# MCU.net
KiCad netlist of a schematic drawn in Altium Designer
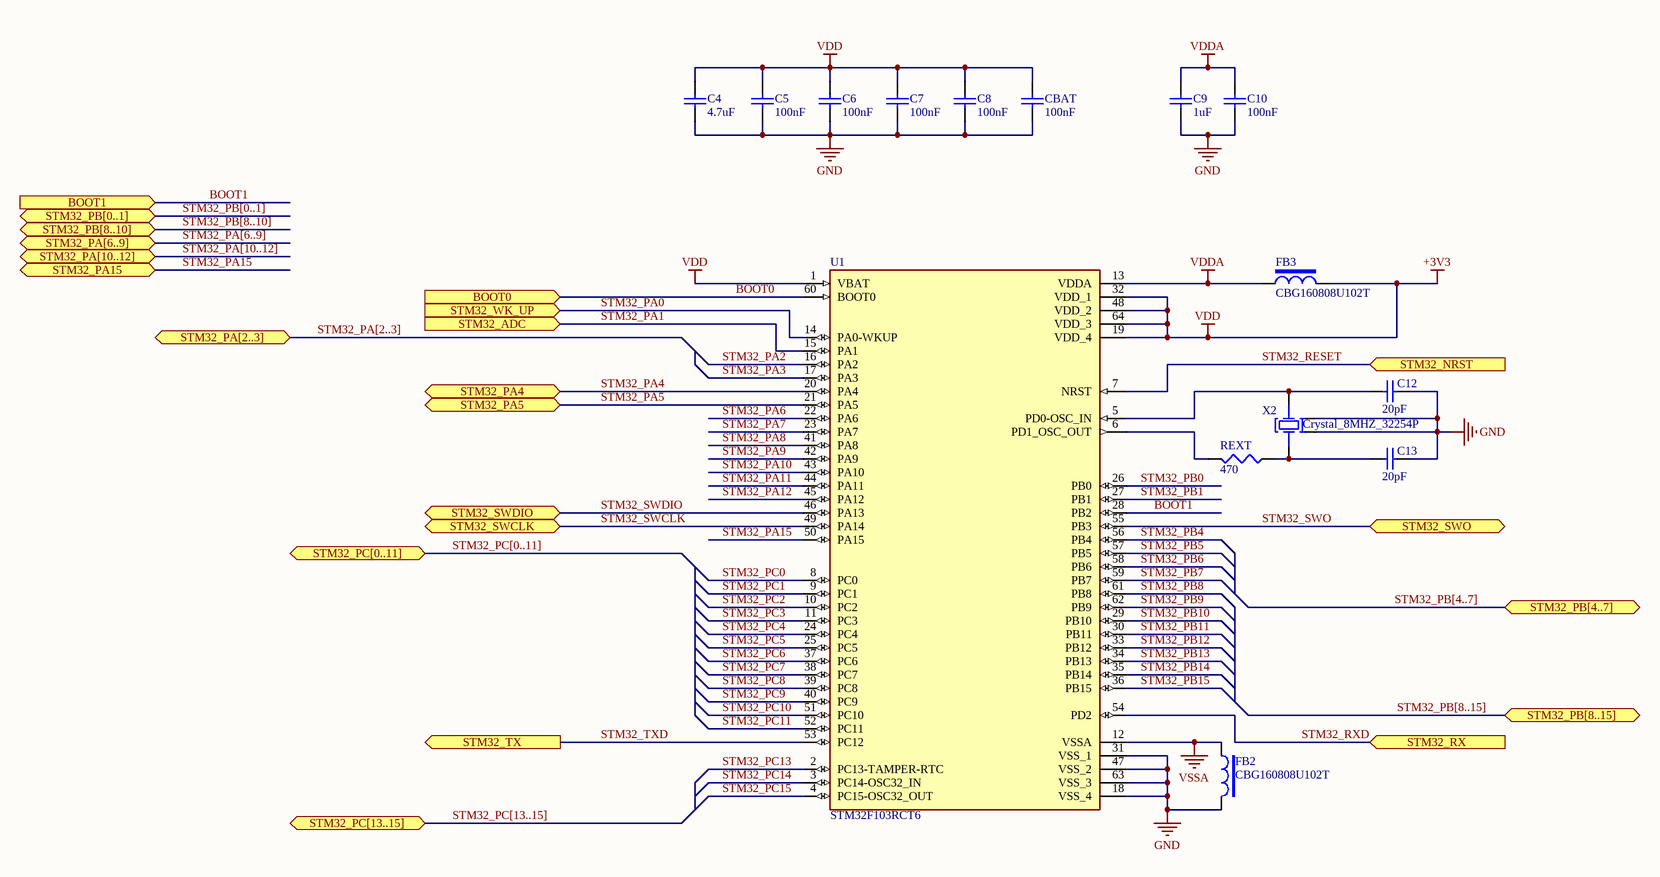
[diagram p0: MCU.SchDoc]

(export (version "E")
  (design (tool "Eeschema 10.0.6"))
  (components
    (comp (ref "C4")
      (value "4.7uF")
      (footprint "CAPC0805(2012)145_L")
      (description "Chip Capacitor, 100nF +/-40%, 16V, 0805, Thickness 1.45 mm")
      (fields (field (name "TOLERANCE") "5%") (field (name "Comment") "100nF"))
      (libsource (lib "Ho Chi Minh City University of Technology") (part "CAP-NP-2"))
    )
    (comp (ref "C5")
      (value "100nF")
      (footprint "CAPC0805(2012)145_L")
      (description "Chip Capacitor, 100nF +/-40%, 16V, 0805, Thickness 1.45 mm")
      (fields (field (name "TOLERANCE") "5%"))
      (libsource (lib "Ho Chi Minh City University of Technology") (part "CAP-NP-2"))
    )
    (comp (ref "C6")
      (value "100nF")
      (footprint "CAPC0805(2012)145_L")
      (description "Chip Capacitor, 100nF +/-40%, 16V, 0805, Thickness 1.45 mm")
      (fields (field (name "TOLERANCE") "5%"))
      (libsource (lib "Ho Chi Minh City University of Technology") (part "CAP-NP-2"))
    )
    (comp (ref "C7")
      (value "100nF")
      (footprint "CAPC0805(2012)145_L")
      (description "Chip Capacitor, 100nF +/-40%, 16V, 0805, Thickness 1.45 mm")
      (fields (field (name "TOLERANCE") "5%"))
      (libsource (lib "Ho Chi Minh City University of Technology") (part "CAP-NP-2"))
    )
    (comp (ref "C8")
      (value "100nF")
      (footprint "CAPC0805(2012)145_L")
      (description "Chip Capacitor, 100nF +/-40%, 16V, 0805, Thickness 1.45 mm")
      (fields (field (name "TOLERANCE") "5%"))
      (libsource (lib "Ho Chi Minh City University of Technology") (part "CAP-NP-2"))
    )
    (comp (ref "C9")
      (value "1uF")
      (footprint "CAPC0805(2012)145_L")
      (description "Chip Capacitor, 100nF +/-40%, 16V, 0805, Thickness 1.45 mm")
      (fields (field (name "TOLERANCE") "5%") (field (name "Comment") "100nF"))
      (libsource (lib "Ho Chi Minh City University of Technology") (part "CAP-NP-2"))
    )
    (comp (ref "C10")
      (value "100nF")
      (footprint "CAPC0805(2012)145_L")
      (description "Chip Capacitor, 100nF +/-40%, 16V, 0805, Thickness 1.45 mm")
      (fields (field (name "TOLERANCE") "5%"))
      (libsource (lib "Ho Chi Minh City University of Technology") (part "CAP-NP-2"))
    )
    (comp (ref "C12")
      (value "20pF")
      (footprint "CAPC0805(2012)145_L")
      (description "Chip Capacitor, 22µF +/-40%, 16V, 0805, Thickness 1.45 mm")
      (fields (field (name "TOLERANCE") "5%") (field (name "Comment") "22uF"))
      (libsource (lib "Ho Chi Minh City University of Technology") (part "CAP-NP-2"))
    )
    (comp (ref "C13")
      (value "20pF")
      (footprint "CAPC0805(2012)145_L")
      (description "Chip Capacitor, 22µF +/-40%, 16V, 0805, Thickness 1.45 mm")
      (fields (field (name "TOLERANCE") "5%") (field (name "Comment") "22uF"))
      (libsource (lib "Ho Chi Minh City University of Technology") (part "CAP-NP-2"))
    )
    (comp (ref "CBAT")
      (value "100nF")
      (footprint "CAPC0805(2012)145_L")
      (description "Chip Capacitor, 100nF +/-40%, 16V, 0805, Thickness 1.45 mm")
      (fields (field (name "TOLERANCE") "5%"))
      (libsource (lib "Ho Chi Minh City University of Technology") (part "CAP-NP-2"))
    )
    (comp (ref "FB2")
      (value "CBG160808U102T")
      (footprint "0603")
      (description "Oreki")
      (fields (field (name "JLCPCB PART #") "C98501"))
      (libsource (lib "Ho Chi Minh City University of Technology") (part "Ferrite Bead"))
    )
    (comp (ref "FB3")
      (value "CBG160808U102T")
      (footprint "0603")
      (description "Oreki")
      (fields (field (name "JLCPCB PART #") "C98501"))
      (libsource (lib "") (part "Ferrite Bead_1"))
    )
    (comp (ref "REXT")
      (value "470")
      (footprint "0805 (2012 Metric)")
      (description "Oreki")
      (fields (field (name "Comment") "220"))
      (libsource (lib "Ho Chi Minh City University of Technology") (part "RES-2"))
    )
    (comp (ref "U1")
      (value "STM32F103RCT6")
      (footprint "QFP50P1200X1200X160-64N")
      (description "ARMÂ® CortexÂ®-M3 STM32F1 Microcontroller IC 32-Bit 72MHz 256KB (256K x 8) FLASH 64-LQFP (10x10)")
      (fields (field (name "MF") "STMicroelectronics") (field (name "JLCPCB PART #") "C8323"))
      (libsource (lib "Ho Chi Minh City University of Technology") (part "STM32F103RCT6"))
    )
    (comp (ref "X2")
      (value "Crystal_8MHZ_32254P")
      (footprint "4-SMD, No Lead (3.2mm x 2.5mm)")
      (description "SMD3225-4P")
      (fields (field (name "JLCPCB PART #") "C2682774"))
      (libsource (lib "Ho Chi Minh City University of Technology") (part "Crystal"))
    )
  )
  (nets
    (net (code "1") (name "+3V3") (class "Default")
      (node (ref "C4") (pin "2") (pinfunction "2_2") (pintype "passive"))
      (node (ref "C5") (pin "2") (pinfunction "2_2") (pintype "passive"))
      (node (ref "C6") (pin "2") (pinfunction "2_2") (pintype "passive"))
      (node (ref "C7") (pin "2") (pinfunction "2_2") (pintype "passive"))
      (node (ref "C8") (pin "2") (pinfunction "2_2") (pintype "passive"))
      (node (ref "CBAT") (pin "2") (pinfunction "2_2") (pintype "passive"))
      (node (ref "FB3") (pin "2") (pinfunction "2_2") (pintype "passive"))
      (node (ref "U1") (pin "1") (pinfunction "VBAT_1") (pintype "input"))
      (node (ref "U1") (pin "19") (pinfunction "VDD_4_19") (pintype "power_in"))
      (node (ref "U1") (pin "32") (pinfunction "VDD_1_32") (pintype "power_in"))
      (node (ref "U1") (pin "48") (pinfunction "VDD_2_48") (pintype "power_in"))
      (node (ref "U1") (pin "64") (pinfunction "VDD_3_64") (pintype "power_in"))
    )
    (net (code "2") (name "/BOOT0") (class "Default")
      (node (ref "U1") (pin "60") (pinfunction "BOOT0_60") (pintype "input"))
    )
    (net (code "3") (name "/BOOT1") (class "Default")
      (node (ref "U1") (pin "28") (pinfunction "PB2_28") (pintype "bidirectional"))
    )
    (net (code "4") (name "/STM32_PA0") (class "Default")
      (node (ref "U1") (pin "14") (pinfunction "PA0-WKUP_14") (pintype "bidirectional"))
    )
    (net (code "5") (name "/STM32_PA1") (class "Default")
      (node (ref "U1") (pin "15") (pinfunction "PA1_15") (pintype "bidirectional"))
    )
    (net (code "6") (name "/STM32_PA2") (class "Default")
      (node (ref "U1") (pin "16") (pinfunction "PA2_16") (pintype "bidirectional"))
    )
    (net (code "7") (name "/STM32_PA3") (class "Default")
      (node (ref "U1") (pin "17") (pinfunction "PA3_17") (pintype "bidirectional"))
    )
    (net (code "8") (name "/STM32_PA4") (class "Default")
      (node (ref "U1") (pin "20") (pinfunction "PA4_20") (pintype "bidirectional"))
    )
    (net (code "9") (name "/STM32_PA5") (class "Default")
      (node (ref "U1") (pin "21") (pinfunction "PA5_21") (pintype "bidirectional"))
    )
    (net (code "10") (name "/STM32_PA6") (class "Default")
      (node (ref "U1") (pin "22") (pinfunction "PA6_22") (pintype "bidirectional"))
    )
    (net (code "11") (name "/STM32_PA7") (class "Default")
      (node (ref "U1") (pin "23") (pinfunction "PA7_23") (pintype "bidirectional"))
    )
    (net (code "12") (name "/STM32_PA8") (class "Default")
      (node (ref "U1") (pin "41") (pinfunction "PA8_41") (pintype "bidirectional"))
    )
    (net (code "13") (name "/STM32_PA9") (class "Default")
      (node (ref "U1") (pin "42") (pinfunction "PA9_42") (pintype "bidirectional"))
    )
    (net (code "14") (name "/STM32_PA10") (class "Default")
      (node (ref "U1") (pin "43") (pinfunction "PA10_43") (pintype "bidirectional"))
    )
    (net (code "15") (name "/STM32_PA11") (class "Default")
      (node (ref "U1") (pin "44") (pinfunction "PA11_44") (pintype "bidirectional"))
    )
    (net (code "16") (name "/STM32_PA12") (class "Default")
      (node (ref "U1") (pin "45") (pinfunction "PA12_45") (pintype "bidirectional"))
    )
    (net (code "17") (name "/STM32_PA15") (class "Default")
      (node (ref "U1") (pin "50") (pinfunction "PA15_50") (pintype "bidirectional"))
    )
    (net (code "21") (name "/STM32_PB0") (class "Default")
      (node (ref "U1") (pin "26") (pinfunction "PB0_26") (pintype "bidirectional"))
    )
    (net (code "22") (name "/STM32_PB1") (class "Default")
      (node (ref "U1") (pin "27") (pinfunction "PB1_27") (pintype "bidirectional"))
    )
    (net (code "23") (name "/STM32_PB4") (class "Default")
      (node (ref "U1") (pin "56") (pinfunction "PB4_56") (pintype "bidirectional"))
    )
    (net (code "24") (name "/STM32_PB5") (class "Default")
      (node (ref "U1") (pin "57") (pinfunction "PB5_57") (pintype "bidirectional"))
    )
    (net (code "25") (name "/STM32_PB6") (class "Default")
      (node (ref "U1") (pin "58") (pinfunction "PB6_58") (pintype "bidirectional"))
    )
    (net (code "26") (name "/STM32_PB7") (class "Default")
      (node (ref "U1") (pin "59") (pinfunction "PB7_59") (pintype "bidirectional"))
    )
    (net (code "27") (name "/STM32_PB8") (class "Default")
      (node (ref "U1") (pin "61") (pinfunction "PB8_61") (pintype "bidirectional"))
    )
    (net (code "28") (name "/STM32_PB9") (class "Default")
      (node (ref "U1") (pin "62") (pinfunction "PB9_62") (pintype "bidirectional"))
    )
    (net (code "29") (name "/STM32_PB10") (class "Default")
      (node (ref "U1") (pin "29") (pinfunction "PB10_29") (pintype "bidirectional"))
    )
    (net (code "30") (name "/STM32_PB11") (class "Default")
      (node (ref "U1") (pin "30") (pinfunction "PB11_30") (pintype "bidirectional"))
    )
    (net (code "31") (name "/STM32_PB12") (class "Default")
      (node (ref "U1") (pin "33") (pinfunction "PB12_33") (pintype "bidirectional"))
    )
    (net (code "32") (name "/STM32_PB13") (class "Default")
      (node (ref "U1") (pin "34") (pinfunction "PB13_34") (pintype "bidirectional"))
    )
    (net (code "33") (name "/STM32_PB14") (class "Default")
      (node (ref "U1") (pin "35") (pinfunction "PB14_35") (pintype "bidirectional"))
    )
    (net (code "34") (name "/STM32_PB15") (class "Default")
      (node (ref "U1") (pin "36") (pinfunction "PB15_36") (pintype "bidirectional"))
    )
    (net (code "39") (name "/STM32_PC0") (class "Default")
      (node (ref "U1") (pin "8") (pinfunction "PC0_8") (pintype "bidirectional"))
    )
    (net (code "40") (name "/STM32_PC1") (class "Default")
      (node (ref "U1") (pin "9") (pinfunction "PC1_9") (pintype "bidirectional"))
    )
    (net (code "41") (name "/STM32_PC2") (class "Default")
      (node (ref "U1") (pin "10") (pinfunction "PC2_10") (pintype "bidirectional"))
    )
    (net (code "42") (name "/STM32_PC3") (class "Default")
      (node (ref "U1") (pin "11") (pinfunction "PC3_11") (pintype "bidirectional"))
    )
    (net (code "43") (name "/STM32_PC4") (class "Default")
      (node (ref "U1") (pin "24") (pinfunction "PC4_24") (pintype "bidirectional"))
    )
    (net (code "44") (name "/STM32_PC5") (class "Default")
      (node (ref "U1") (pin "25") (pinfunction "PC5_25") (pintype "bidirectional"))
    )
    (net (code "45") (name "/STM32_PC6") (class "Default")
      (node (ref "U1") (pin "37") (pinfunction "PC6_37") (pintype "bidirectional"))
    )
    (net (code "46") (name "/STM32_PC7") (class "Default")
      (node (ref "U1") (pin "38") (pinfunction "PC7_38") (pintype "bidirectional"))
    )
    (net (code "47") (name "/STM32_PC8") (class "Default")
      (node (ref "U1") (pin "39") (pinfunction "PC8_39") (pintype "bidirectional"))
    )
    (net (code "48") (name "/STM32_PC9") (class "Default")
      (node (ref "U1") (pin "40") (pinfunction "PC9_40") (pintype "bidirectional"))
    )
    (net (code "49") (name "/STM32_PC10") (class "Default")
      (node (ref "U1") (pin "51") (pinfunction "PC10_51") (pintype "bidirectional"))
    )
    (net (code "50") (name "/STM32_PC11") (class "Default")
      (node (ref "U1") (pin "52") (pinfunction "PC11_52") (pintype "bidirectional"))
    )
    (net (code "51") (name "/STM32_PC13") (class "Default")
      (node (ref "U1") (pin "2") (pinfunction "PC13-TAMPER-RTC_2") (pintype "bidirectional"))
    )
    (net (code "52") (name "/STM32_PC14") (class "Default")
      (node (ref "U1") (pin "3") (pinfunction "PC14-OSC32_IN_3") (pintype "bidirectional"))
    )
    (net (code "53") (name "/STM32_PC15") (class "Default")
      (node (ref "U1") (pin "4") (pinfunction "PC15-OSC32_OUT_4") (pintype "bidirectional"))
    )
    (net (code "56") (name "/STM32_RESET") (class "Default")
      (node (ref "U1") (pin "7") (pinfunction "NRST_7") (pintype "input"))
    )
    (net (code "57") (name "/STM32_RXD") (class "Default")
      (node (ref "U1") (pin "54") (pinfunction "PD2_54") (pintype "bidirectional"))
    )
    (net (code "58") (name "/STM32_SWCLK") (class "Default")
      (node (ref "U1") (pin "49") (pinfunction "PA14_49") (pintype "bidirectional"))
    )
    (net (code "59") (name "/STM32_SWDIO") (class "Default")
      (node (ref "U1") (pin "46") (pinfunction "PA13_46") (pintype "bidirectional"))
    )
    (net (code "60") (name "/STM32_SWO") (class "Default")
      (node (ref "U1") (pin "55") (pinfunction "PB3_55") (pintype "bidirectional"))
    )
    (net (code "61") (name "/STM32_TXD") (class "Default")
      (node (ref "U1") (pin "53") (pinfunction "PC12_53") (pintype "bidirectional"))
    )
    (net (code "62") (name "GND") (class "Default")
      (node (ref "C10") (pin "1") (pinfunction "1_1") (pintype "passive"))
      (node (ref "C12") (pin "2") (pinfunction "2_2") (pintype "passive"))
      (node (ref "C13") (pin "2") (pinfunction "2_2") (pintype "passive"))
      (node (ref "C4") (pin "1") (pinfunction "1_1") (pintype "passive"))
      (node (ref "C5") (pin "1") (pinfunction "1_1") (pintype "passive"))
      (node (ref "C6") (pin "1") (pinfunction "1_1") (pintype "passive"))
      (node (ref "C7") (pin "1") (pinfunction "1_1") (pintype "passive"))
      (node (ref "C8") (pin "1") (pinfunction "1_1") (pintype "passive"))
      (node (ref "C9") (pin "1") (pinfunction "1_1") (pintype "passive"))
      (node (ref "CBAT") (pin "1") (pinfunction "1_1") (pintype "passive"))
      (node (ref "FB2") (pin "2") (pinfunction "2_2") (pintype "passive"))
      (node (ref "U1") (pin "18") (pinfunction "VSS_4_18") (pintype "power_in"))
      (node (ref "U1") (pin "31") (pinfunction "VSS_1_31") (pintype "power_in"))
      (node (ref "U1") (pin "47") (pinfunction "VSS_2_47") (pintype "power_in"))
      (node (ref "U1") (pin "63") (pinfunction "VSS_3_63") (pintype "power_in"))
      (node (ref "X2") (pin "2") (pinfunction "GND_2") (pintype "passive"))
      (node (ref "X2") (pin "4") (pinfunction "GND_4") (pintype "passive"))
    )
    (net (code "63") (name "Net-(C13-Pad1)") (class "Default")
      (node (ref "C13") (pin "1") (pinfunction "1_1") (pintype "passive"))
      (node (ref "REXT") (pin "1") (pinfunction "1_1") (pintype "passive"))
      (node (ref "X2") (pin "1") (pinfunction "1_1") (pintype "passive"))
    )
    (net (code "64") (name "Net-(U1-PD0-OSC_IN)") (class "Default")
      (node (ref "C12") (pin "1") (pinfunction "1_1") (pintype "passive"))
      (node (ref "U1") (pin "5") (pinfunction "PD0-OSC_IN_5") (pintype "input"))
      (node (ref "X2") (pin "3") (pinfunction "3_3") (pintype "passive"))
    )
    (net (code "65") (name "Net-(U1-PD1_OSC_OUT)") (class "Default")
      (node (ref "REXT") (pin "2") (pinfunction "2_2") (pintype "passive"))
      (node (ref "U1") (pin "6") (pinfunction "PD1_OSC_OUT_6") (pintype "output"))
    )
    (net (code "66") (name "VDDA") (class "Default")
      (node (ref "C10") (pin "2") (pinfunction "2_2") (pintype "passive"))
      (node (ref "C9") (pin "2") (pinfunction "2_2") (pintype "passive"))
      (node (ref "FB3") (pin "1") (pinfunction "1_1") (pintype "passive"))
      (node (ref "U1") (pin "13") (pinfunction "VDDA_13") (pintype "power_in"))
    )
    (net (code "67") (name "VSSA") (class "Default")
      (node (ref "FB2") (pin "1") (pinfunction "1_1") (pintype "passive"))
      (node (ref "U1") (pin "12") (pinfunction "VSSA_12") (pintype "power_in"))
    )
  )
)
